# 04_FPGA_core.net
KiCad netlist of a schematic drawn in Altium Designer
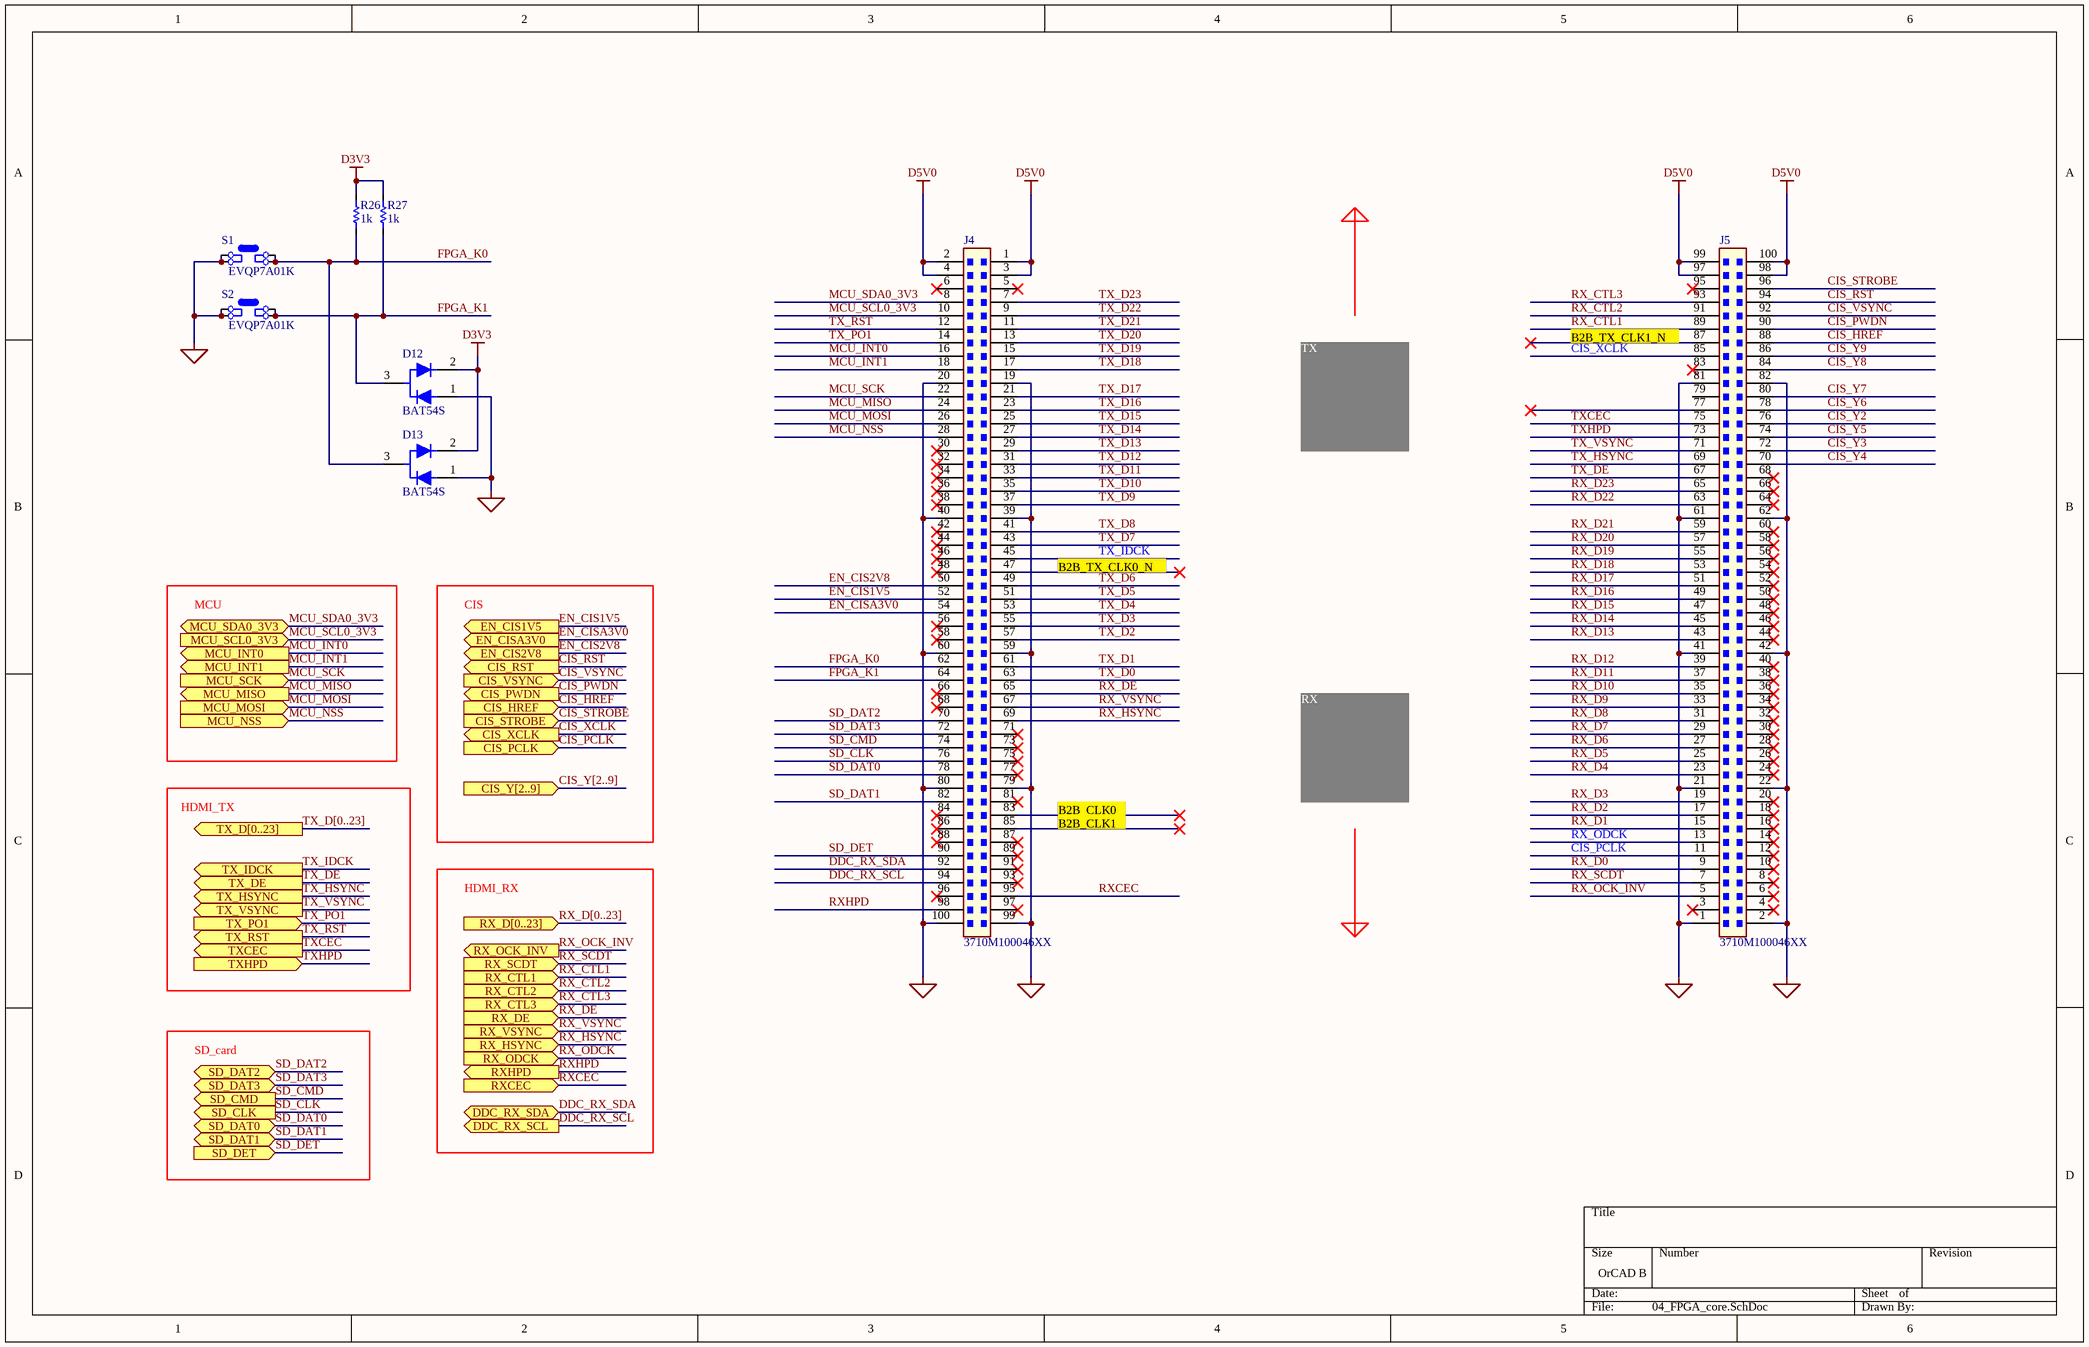
[diagram p0: 04_FPGA_core.SchDoc]

(export (version "E")
  (design (tool "Eeschema 10.0.6"))
  (components
    (comp (ref "D12")
      (value "BAT54S")
      (footprint "SOT95P230X110-3N_SOT23_BAT54")
      (description "Schottky Double Diodes,30V,200mA,SOT23,a1k2k1a2")
      (libsource (lib "AD15_schlib") (part "BAT54S"))
    )
    (comp (ref "D13")
      (value "BAT54S")
      (footprint "SOT95P230X110-3N_SOT23_BAT54")
      (description "Schottky Double Diodes,30V,200mA,SOT23,a1k2k1a2")
      (libsource (lib "AD15_schlib") (part "BAT54S"))
    )
    (comp (ref "J4")
      (value "3710M100046XX")
      (footprint "3710M100046XX")
      (description "B2B male,100Pin,Vertical,0.8mm Pitch,SMD")
      (libsource (lib "AD15_schlib") (part "3710M100046XX"))
    )
    (comp (ref "J5")
      (value "3710M100046XX")
      (footprint "3710M100046XX")
      (description "B2B male,100Pin,Vertical,0.8mm Pitch,SMD")
      (libsource (lib "AD15_schlib") (part "3710M100046XX"))
    )
    (comp (ref "R26")
      (value "1k")
      (footprint "R0402")
      (description "RES,1k,1%,1/16W,0402")
      (libsource (lib "R0402") (part "RES011"))
    )
    (comp (ref "R27")
      (value "1k")
      (footprint "R0402")
      (description "RES,1k,1%,1/16W,0402")
      (libsource (lib "R0402") (part "RES011"))
    )
    (comp (ref "S1")
      (value "EVQP7A01K")
      (footprint "EVQP7A01K")
      (description "Switch,3.5x2.9,Normal open,SMD")
      (libsource (lib "AD15_libpkg") (part "EVQP7A01K"))
    )
    (comp (ref "S2")
      (value "EVQP7A01K")
      (footprint "EVQP7A01K")
      (description "Switch,3.5x2.9,Normal open,SMD")
      (libsource (lib "AD15_libpkg") (part "EVQP7A01K"))
    )
  )
  (nets
    (net (code "1") (name "/CIS_HREF") (class "Default")
      (node (ref "J5") (pin "88") (pinfunction "88_88") (pintype "passive"))
    )
    (net (code "2") (name "/CIS_PCLK") (class "Default")
      (node (ref "J5") (pin "11") (pinfunction "11_11") (pintype "passive"))
    )
    (net (code "3") (name "/CIS_PWDN") (class "Default")
      (node (ref "J5") (pin "90") (pinfunction "90_90") (pintype "passive"))
    )
    (net (code "4") (name "/CIS_RST") (class "Default")
      (node (ref "J5") (pin "94") (pinfunction "94_94") (pintype "passive"))
    )
    (net (code "5") (name "/CIS_STROBE") (class "Default")
      (node (ref "J5") (pin "96") (pinfunction "96_96") (pintype "passive"))
    )
    (net (code "6") (name "/CIS_VSYNC") (class "Default")
      (node (ref "J5") (pin "92") (pinfunction "92_92") (pintype "passive"))
    )
    (net (code "7") (name "/CIS_XCLK") (class "Default")
      (node (ref "J5") (pin "85") (pinfunction "85_85") (pintype "passive"))
    )
    (net (code "8") (name "/CIS_Y2") (class "Default")
      (node (ref "J5") (pin "76") (pinfunction "76_76") (pintype "passive"))
    )
    (net (code "9") (name "/CIS_Y3") (class "Default")
      (node (ref "J5") (pin "72") (pinfunction "72_72") (pintype "passive"))
    )
    (net (code "10") (name "/CIS_Y4") (class "Default")
      (node (ref "J5") (pin "70") (pinfunction "70_70") (pintype "passive"))
    )
    (net (code "11") (name "/CIS_Y5") (class "Default")
      (node (ref "J5") (pin "74") (pinfunction "74_74") (pintype "passive"))
    )
    (net (code "12") (name "/CIS_Y6") (class "Default")
      (node (ref "J5") (pin "78") (pinfunction "78_78") (pintype "passive"))
    )
    (net (code "13") (name "/CIS_Y7") (class "Default")
      (node (ref "J5") (pin "80") (pinfunction "80_80") (pintype "passive"))
    )
    (net (code "14") (name "/CIS_Y8") (class "Default")
      (node (ref "J5") (pin "84") (pinfunction "84_84") (pintype "passive"))
    )
    (net (code "15") (name "/CIS_Y9") (class "Default")
      (node (ref "J5") (pin "86") (pinfunction "86_86") (pintype "passive"))
    )
    (net (code "17") (name "/DDC_RX_SCL") (class "Default")
      (node (ref "J4") (pin "94") (pinfunction "94_94") (pintype "passive"))
    )
    (net (code "18") (name "/DDC_RX_SDA") (class "Default")
      (node (ref "J4") (pin "92") (pinfunction "92_92") (pintype "passive"))
    )
    (net (code "19") (name "/EN_CIS1V5") (class "Default")
      (node (ref "J4") (pin "52") (pinfunction "52_52") (pintype "passive"))
    )
    (net (code "20") (name "/EN_CIS2V8") (class "Default")
      (node (ref "J4") (pin "50") (pinfunction "50_50") (pintype "passive"))
    )
    (net (code "21") (name "/EN_CISA3V0") (class "Default")
      (node (ref "J4") (pin "54") (pinfunction "54_54") (pintype "passive"))
    )
    (net (code "22") (name "/FPGA_K0") (class "Default")
      (node (ref "D13") (pin "3") (pinfunction "2_3") (pintype "passive"))
      (node (ref "J4") (pin "62") (pinfunction "62_62") (pintype "passive"))
      (node (ref "R26") (pin "1") (pinfunction "0_1") (pintype "passive"))
      (node (ref "S1") (pin "2") (pinfunction "CVdd_2") (pintype "passive"))
    )
    (net (code "23") (name "/FPGA_K1") (class "Default")
      (node (ref "D12") (pin "3") (pinfunction "2_3") (pintype "passive"))
      (node (ref "J4") (pin "64") (pinfunction "64_64") (pintype "passive"))
      (node (ref "R27") (pin "1") (pinfunction "0_1") (pintype "passive"))
      (node (ref "S2") (pin "2") (pinfunction "CVdd_2") (pintype "passive"))
    )
    (net (code "24") (name "/MCU_INT0") (class "Default")
      (node (ref "J4") (pin "16") (pinfunction "16_16") (pintype "passive"))
    )
    (net (code "25") (name "/MCU_INT1") (class "Default")
      (node (ref "J4") (pin "18") (pinfunction "18_18") (pintype "passive"))
    )
    (net (code "26") (name "/MCU_MISO") (class "Default")
      (node (ref "J4") (pin "24") (pinfunction "24_24") (pintype "passive"))
    )
    (net (code "27") (name "/MCU_MOSI") (class "Default")
      (node (ref "J4") (pin "26") (pinfunction "26_26") (pintype "passive"))
    )
    (net (code "28") (name "/MCU_NSS") (class "Default")
      (node (ref "J4") (pin "28") (pinfunction "28_28") (pintype "passive"))
    )
    (net (code "29") (name "/MCU_SCK") (class "Default")
      (node (ref "J4") (pin "22") (pinfunction "22_22") (pintype "passive"))
    )
    (net (code "30") (name "/MCU_SCL0_3V3") (class "Default")
      (node (ref "J4") (pin "10") (pinfunction "9_10") (pintype "passive"))
    )
    (net (code "31") (name "/MCU_SDA0_3V3") (class "Default")
      (node (ref "J4") (pin "8") (pinfunction "7_8") (pintype "passive"))
    )
    (net (code "32") (name "/RXCEC") (class "Default")
      (node (ref "J4") (pin "95") (pinfunction "95_95") (pintype "passive"))
    )
    (net (code "33") (name "/RXHPD") (class "Default")
      (node (ref "J4") (pin "98") (pinfunction "98_98") (pintype "passive"))
    )
    (net (code "34") (name "/RX_CTL1") (class "Default")
      (node (ref "J5") (pin "89") (pinfunction "89_89") (pintype "passive"))
    )
    (net (code "35") (name "/RX_CTL2") (class "Default")
      (node (ref "J5") (pin "91") (pinfunction "91_91") (pintype "passive"))
    )
    (net (code "36") (name "/RX_CTL3") (class "Default")
      (node (ref "J5") (pin "93") (pinfunction "93_93") (pintype "passive"))
    )
    (net (code "37") (name "/RX_D0") (class "Default")
      (node (ref "J5") (pin "9") (pinfunction "8_9") (pintype "passive"))
    )
    (net (code "38") (name "/RX_D1") (class "Default")
      (node (ref "J5") (pin "15") (pinfunction "15_15") (pintype "passive"))
    )
    (net (code "39") (name "/RX_D2") (class "Default")
      (node (ref "J5") (pin "17") (pinfunction "17_17") (pintype "passive"))
    )
    (net (code "40") (name "/RX_D3") (class "Default")
      (node (ref "J5") (pin "19") (pinfunction "19_19") (pintype "passive"))
    )
    (net (code "41") (name "/RX_D4") (class "Default")
      (node (ref "J5") (pin "23") (pinfunction "23_23") (pintype "passive"))
    )
    (net (code "42") (name "/RX_D5") (class "Default")
      (node (ref "J5") (pin "25") (pinfunction "25_25") (pintype "passive"))
    )
    (net (code "43") (name "/RX_D6") (class "Default")
      (node (ref "J5") (pin "27") (pinfunction "27_27") (pintype "passive"))
    )
    (net (code "44") (name "/RX_D7") (class "Default")
      (node (ref "J5") (pin "29") (pinfunction "29_29") (pintype "passive"))
    )
    (net (code "45") (name "/RX_D8") (class "Default")
      (node (ref "J5") (pin "31") (pinfunction "31_31") (pintype "passive"))
    )
    (net (code "46") (name "/RX_D9") (class "Default")
      (node (ref "J5") (pin "33") (pinfunction "33_33") (pintype "passive"))
    )
    (net (code "47") (name "/RX_D10") (class "Default")
      (node (ref "J5") (pin "35") (pinfunction "35_35") (pintype "passive"))
    )
    (net (code "48") (name "/RX_D11") (class "Default")
      (node (ref "J5") (pin "37") (pinfunction "37_37") (pintype "passive"))
    )
    (net (code "49") (name "/RX_D12") (class "Default")
      (node (ref "J5") (pin "39") (pinfunction "39_39") (pintype "passive"))
    )
    (net (code "50") (name "/RX_D13") (class "Default")
      (node (ref "J5") (pin "43") (pinfunction "43_43") (pintype "passive"))
    )
    (net (code "51") (name "/RX_D14") (class "Default")
      (node (ref "J5") (pin "45") (pinfunction "45_45") (pintype "passive"))
    )
    (net (code "52") (name "/RX_D15") (class "Default")
      (node (ref "J5") (pin "47") (pinfunction "47_47") (pintype "passive"))
    )
    (net (code "53") (name "/RX_D16") (class "Default")
      (node (ref "J5") (pin "49") (pinfunction "49_49") (pintype "passive"))
    )
    (net (code "54") (name "/RX_D17") (class "Default")
      (node (ref "J5") (pin "51") (pinfunction "51_51") (pintype "passive"))
    )
    (net (code "55") (name "/RX_D18") (class "Default")
      (node (ref "J5") (pin "53") (pinfunction "53_53") (pintype "passive"))
    )
    (net (code "56") (name "/RX_D19") (class "Default")
      (node (ref "J5") (pin "55") (pinfunction "55_55") (pintype "passive"))
    )
    (net (code "57") (name "/RX_D20") (class "Default")
      (node (ref "J5") (pin "57") (pinfunction "57_57") (pintype "passive"))
    )
    (net (code "58") (name "/RX_D21") (class "Default")
      (node (ref "J5") (pin "59") (pinfunction "59_59") (pintype "passive"))
    )
    (net (code "59") (name "/RX_D22") (class "Default")
      (node (ref "J5") (pin "63") (pinfunction "63_63") (pintype "passive"))
    )
    (net (code "60") (name "/RX_D23") (class "Default")
      (node (ref "J5") (pin "65") (pinfunction "65_65") (pintype "passive"))
    )
    (net (code "61") (name "/RX_DE") (class "Default")
      (node (ref "J4") (pin "65") (pinfunction "65_65") (pintype "passive"))
    )
    (net (code "63") (name "/RX_HSYNC") (class "Default")
      (node (ref "J4") (pin "69") (pinfunction "69_69") (pintype "passive"))
    )
    (net (code "64") (name "/RX_OCK_INV") (class "Default")
      (node (ref "J5") (pin "5") (pinfunction "4_5") (pintype "passive"))
    )
    (net (code "65") (name "/RX_ODCK") (class "Default")
      (node (ref "J5") (pin "13") (pinfunction "13_13") (pintype "passive"))
    )
    (net (code "66") (name "/RX_SCDT") (class "Default")
      (node (ref "J5") (pin "7") (pinfunction "6_7") (pintype "passive"))
    )
    (net (code "67") (name "/RX_VSYNC") (class "Default")
      (node (ref "J4") (pin "67") (pinfunction "67_67") (pintype "passive"))
    )
    (net (code "68") (name "/SD_CLK") (class "Default")
      (node (ref "J4") (pin "76") (pinfunction "76_76") (pintype "passive"))
    )
    (net (code "69") (name "/SD_CMD") (class "Default")
      (node (ref "J4") (pin "74") (pinfunction "74_74") (pintype "passive"))
    )
    (net (code "70") (name "/SD_DAT0") (class "Default")
      (node (ref "J4") (pin "78") (pinfunction "78_78") (pintype "passive"))
    )
    (net (code "71") (name "/SD_DAT1") (class "Default")
      (node (ref "J4") (pin "82") (pinfunction "82_82") (pintype "passive"))
    )
    (net (code "72") (name "/SD_DAT2") (class "Default")
      (node (ref "J4") (pin "70") (pinfunction "70_70") (pintype "passive"))
    )
    (net (code "73") (name "/SD_DAT3") (class "Default")
      (node (ref "J4") (pin "72") (pinfunction "72_72") (pintype "passive"))
    )
    (net (code "74") (name "/SD_DET") (class "Default")
      (node (ref "J4") (pin "90") (pinfunction "90_90") (pintype "passive"))
    )
    (net (code "75") (name "/TXCEC") (class "Default")
      (node (ref "J5") (pin "75") (pinfunction "75_75") (pintype "passive"))
    )
    (net (code "76") (name "/TXHPD") (class "Default")
      (node (ref "J5") (pin "73") (pinfunction "73_73") (pintype "passive"))
    )
    (net (code "77") (name "/TX_D0") (class "Default")
      (node (ref "J4") (pin "63") (pinfunction "63_63") (pintype "passive"))
    )
    (net (code "78") (name "/TX_D1") (class "Default")
      (node (ref "J4") (pin "61") (pinfunction "61_61") (pintype "passive"))
    )
    (net (code "79") (name "/TX_D2") (class "Default")
      (node (ref "J4") (pin "57") (pinfunction "57_57") (pintype "passive"))
    )
    (net (code "80") (name "/TX_D3") (class "Default")
      (node (ref "J4") (pin "55") (pinfunction "55_55") (pintype "passive"))
    )
    (net (code "81") (name "/TX_D4") (class "Default")
      (node (ref "J4") (pin "53") (pinfunction "53_53") (pintype "passive"))
    )
    (net (code "82") (name "/TX_D5") (class "Default")
      (node (ref "J4") (pin "51") (pinfunction "51_51") (pintype "passive"))
    )
    (net (code "83") (name "/TX_D6") (class "Default")
      (node (ref "J4") (pin "49") (pinfunction "49_49") (pintype "passive"))
    )
    (net (code "84") (name "/TX_D7") (class "Default")
      (node (ref "J4") (pin "43") (pinfunction "43_43") (pintype "passive"))
    )
    (net (code "85") (name "/TX_D8") (class "Default")
      (node (ref "J4") (pin "41") (pinfunction "41_41") (pintype "passive"))
    )
    (net (code "86") (name "/TX_D9") (class "Default")
      (node (ref "J4") (pin "37") (pinfunction "37_37") (pintype "passive"))
    )
    (net (code "87") (name "/TX_D10") (class "Default")
      (node (ref "J4") (pin "35") (pinfunction "35_35") (pintype "passive"))
    )
    (net (code "88") (name "/TX_D11") (class "Default")
      (node (ref "J4") (pin "33") (pinfunction "33_33") (pintype "passive"))
    )
    (net (code "89") (name "/TX_D12") (class "Default")
      (node (ref "J4") (pin "31") (pinfunction "31_31") (pintype "passive"))
    )
    (net (code "90") (name "/TX_D13") (class "Default")
      (node (ref "J4") (pin "29") (pinfunction "29_29") (pintype "passive"))
    )
    (net (code "91") (name "/TX_D14") (class "Default")
      (node (ref "J4") (pin "27") (pinfunction "27_27") (pintype "passive"))
    )
    (net (code "92") (name "/TX_D15") (class "Default")
      (node (ref "J4") (pin "25") (pinfunction "25_25") (pintype "passive"))
    )
    (net (code "93") (name "/TX_D16") (class "Default")
      (node (ref "J4") (pin "23") (pinfunction "23_23") (pintype "passive"))
    )
    (net (code "94") (name "/TX_D17") (class "Default")
      (node (ref "J4") (pin "21") (pinfunction "21_21") (pintype "passive"))
    )
    (net (code "95") (name "/TX_D18") (class "Default")
      (node (ref "J4") (pin "17") (pinfunction "17_17") (pintype "passive"))
    )
    (net (code "96") (name "/TX_D19") (class "Default")
      (node (ref "J4") (pin "15") (pinfunction "15_15") (pintype "passive"))
    )
    (net (code "97") (name "/TX_D20") (class "Default")
      (node (ref "J4") (pin "13") (pinfunction "13_13") (pintype "passive"))
    )
    (net (code "98") (name "/TX_D21") (class "Default")
      (node (ref "J4") (pin "11") (pinfunction "11_11") (pintype "passive"))
    )
    (net (code "99") (name "/TX_D22") (class "Default")
      (node (ref "J4") (pin "9") (pinfunction "8_9") (pintype "passive"))
    )
    (net (code "100") (name "/TX_D23") (class "Default")
      (node (ref "J4") (pin "7") (pinfunction "6_7") (pintype "passive"))
    )
    (net (code "101") (name "/TX_DE") (class "Default")
      (node (ref "J5") (pin "67") (pinfunction "67_67") (pintype "passive"))
    )
    (net (code "103") (name "/TX_HSYNC") (class "Default")
      (node (ref "J5") (pin "69") (pinfunction "69_69") (pintype "passive"))
    )
    (net (code "104") (name "/TX_IDCK") (class "Default")
      (node (ref "J4") (pin "45") (pinfunction "45_45") (pintype "passive"))
    )
    (net (code "105") (name "/TX_PO1") (class "Default")
      (node (ref "J4") (pin "14") (pinfunction "14_14") (pintype "passive"))
    )
    (net (code "106") (name "/TX_RST") (class "Default")
      (node (ref "J4") (pin "12") (pinfunction "12_12") (pintype "passive"))
    )
    (net (code "107") (name "/TX_VSYNC") (class "Default")
      (node (ref "J5") (pin "71") (pinfunction "71_71") (pintype "passive"))
    )
    (net (code "108") (name "D3V3") (class "Default")
      (node (ref "D12") (pin "2") (pinfunction "1_2") (pintype "passive"))
      (node (ref "D13") (pin "2") (pinfunction "1_2") (pintype "passive"))
      (node (ref "R26") (pin "2") (pinfunction "2_2") (pintype "passive"))
      (node (ref "R27") (pin "2") (pinfunction "2_2") (pintype "passive"))
    )
    (net (code "109") (name "D5V0") (class "Default")
      (node (ref "J4") (pin "1") (pinfunction "0_1") (pintype "passive"))
      (node (ref "J4") (pin "2") (pinfunction "1_2") (pintype "passive"))
      (node (ref "J4") (pin "3") (pinfunction "2_3") (pintype "passive"))
      (node (ref "J4") (pin "4") (pinfunction "3_4") (pintype "passive"))
      (node (ref "J5") (pin "100") (pinfunction "100_100") (pintype "passive"))
      (node (ref "J5") (pin "97") (pinfunction "97_97") (pintype "passive"))
      (node (ref "J5") (pin "98") (pinfunction "98_98") (pintype "passive"))
      (node (ref "J5") (pin "99") (pinfunction "99_99") (pintype "passive"))
    )
    (net (code "110") (name "GND") (class "Default")
      (node (ref "D12") (pin "1") (pinfunction "0_1") (pintype "passive"))
      (node (ref "D13") (pin "1") (pinfunction "0_1") (pintype "passive"))
      (node (ref "J4") (pin "100") (pinfunction "100_100") (pintype "passive"))
      (node (ref "J4") (pin "19") (pinfunction "19_19") (pintype "passive"))
      (node (ref "J4") (pin "20") (pinfunction "20_20") (pintype "passive"))
      (node (ref "J4") (pin "39") (pinfunction "39_39") (pintype "passive"))
      (node (ref "J4") (pin "40") (pinfunction "40_40") (pintype "passive"))
      (node (ref "J4") (pin "59") (pinfunction "59_59") (pintype "passive"))
      (node (ref "J4") (pin "60") (pinfunction "60_60") (pintype "passive"))
      (node (ref "J4") (pin "79") (pinfunction "79_79") (pintype "passive"))
      (node (ref "J4") (pin "80") (pinfunction "80_80") (pintype "passive"))
      (node (ref "J4") (pin "99") (pinfunction "99_99") (pintype "passive"))
      (node (ref "J5") (pin "1") (pinfunction "0_1") (pintype "passive"))
      (node (ref "J5") (pin "2") (pinfunction "1_2") (pintype "passive"))
      (node (ref "J5") (pin "21") (pinfunction "21_21") (pintype "passive"))
      (node (ref "J5") (pin "22") (pinfunction "22_22") (pintype "passive"))
      (node (ref "J5") (pin "41") (pinfunction "41_41") (pintype "passive"))
      (node (ref "J5") (pin "42") (pinfunction "42_42") (pintype "passive"))
      (node (ref "J5") (pin "61") (pinfunction "61_61") (pintype "passive"))
      (node (ref "J5") (pin "62") (pinfunction "62_62") (pintype "passive"))
      (node (ref "J5") (pin "81") (pinfunction "81_81") (pintype "passive"))
      (node (ref "J5") (pin "82") (pinfunction "82_82") (pintype "passive"))
      (node (ref "S1") (pin "1") (pinfunction "CVdd_1") (pintype "passive"))
      (node (ref "S2") (pin "1") (pinfunction "CVdd_1") (pintype "passive"))
    )
    (net (code "111") (name "unconnected-(J4-4-Pad5)") (class "Default")
      (node (ref "J4") (pin "5") (pinfunction "4_5") (pintype "passive+no_connect"))
    )
    (net (code "112") (name "unconnected-(J4-5-Pad6)") (class "Default")
      (node (ref "J4") (pin "6") (pinfunction "5_6") (pintype "passive+no_connect"))
    )
    (net (code "113") (name "unconnected-(J4-Pad30)") (class "Default")
      (node (ref "J4") (pin "30") (pinfunction "30_30") (pintype "passive+no_connect"))
    )
    (net (code "114") (name "unconnected-(J4-Pad32)") (class "Default")
      (node (ref "J4") (pin "32") (pinfunction "32_32") (pintype "passive+no_connect"))
    )
    (net (code "115") (name "unconnected-(J4-Pad34)") (class "Default")
      (node (ref "J4") (pin "34") (pinfunction "34_34") (pintype "passive+no_connect"))
    )
    (net (code "116") (name "unconnected-(J4-Pad36)") (class "Default")
      (node (ref "J4") (pin "36") (pinfunction "36_36") (pintype "passive+no_connect"))
    )
    (net (code "117") (name "unconnected-(J4-Pad38)") (class "Default")
      (node (ref "J4") (pin "38") (pinfunction "38_38") (pintype "passive+no_connect"))
    )
    (net (code "118") (name "unconnected-(J4-Pad42)") (class "Default")
      (node (ref "J4") (pin "42") (pinfunction "42_42") (pintype "passive+no_connect"))
    )
    (net (code "119") (name "unconnected-(J4-Pad44)") (class "Default")
      (node (ref "J4") (pin "44") (pinfunction "44_44") (pintype "passive+no_connect"))
    )
    (net (code "120") (name "unconnected-(J4-Pad46)") (class "Default")
      (node (ref "J4") (pin "46") (pinfunction "46_46") (pintype "passive+no_connect"))
    )
    (net (code "121") (name "unconnected-(J4-Pad47)") (class "Default")
      (node (ref "J4") (pin "47") (pinfunction "47_47") (pintype "passive+no_connect"))
    )
    (net (code "122") (name "unconnected-(J4-Pad48)") (class "Default")
      (node (ref "J4") (pin "48") (pinfunction "48_48") (pintype "passive+no_connect"))
    )
    (net (code "123") (name "unconnected-(J4-Pad56)") (class "Default")
      (node (ref "J4") (pin "56") (pinfunction "56_56") (pintype "passive+no_connect"))
    )
    (net (code "124") (name "unconnected-(J4-Pad58)") (class "Default")
      (node (ref "J4") (pin "58") (pinfunction "58_58") (pintype "passive+no_connect"))
    )
    (net (code "125") (name "unconnected-(J4-Pad66)") (class "Default")
      (node (ref "J4") (pin "66") (pinfunction "66_66") (pintype "passive+no_connect"))
    )
    (net (code "126") (name "unconnected-(J4-Pad68)") (class "Default")
      (node (ref "J4") (pin "68") (pinfunction "68_68") (pintype "passive+no_connect"))
    )
    (net (code "127") (name "unconnected-(J4-Pad71)") (class "Default")
      (node (ref "J4") (pin "71") (pinfunction "71_71") (pintype "passive+no_connect"))
    )
    (net (code "128") (name "unconnected-(J4-Pad73)") (class "Default")
      (node (ref "J4") (pin "73") (pinfunction "73_73") (pintype "passive+no_connect"))
    )
    (net (code "129") (name "unconnected-(J4-Pad75)") (class "Default")
      (node (ref "J4") (pin "75") (pinfunction "75_75") (pintype "passive+no_connect"))
    )
    (net (code "130") (name "unconnected-(J4-Pad77)") (class "Default")
      (node (ref "J4") (pin "77") (pinfunction "77_77") (pintype "passive+no_connect"))
    )
    (net (code "131") (name "unconnected-(J4-Pad81)") (class "Default")
      (node (ref "J4") (pin "81") (pinfunction "81_81") (pintype "passive+no_connect"))
    )
    (net (code "132") (name "unconnected-(J4-Pad83)") (class "Default")
      (node (ref "J4") (pin "83") (pinfunction "83_83") (pintype "passive+no_connect"))
    )
    (net (code "133") (name "unconnected-(J4-Pad84)") (class "Default")
      (node (ref "J4") (pin "84") (pinfunction "84_84") (pintype "passive+no_connect"))
    )
    (net (code "134") (name "unconnected-(J4-Pad85)") (class "Default")
      (node (ref "J4") (pin "85") (pinfunction "85_85") (pintype "passive+no_connect"))
    )
    (net (code "135") (name "unconnected-(J4-Pad86)") (class "Default")
      (node (ref "J4") (pin "86") (pinfunction "86_86") (pintype "passive+no_connect"))
    )
    (net (code "136") (name "unconnected-(J4-Pad87)") (class "Default")
      (node (ref "J4") (pin "87") (pinfunction "87_87") (pintype "passive+no_connect"))
    )
    (net (code "137") (name "unconnected-(J4-Pad88)") (class "Default")
      (node (ref "J4") (pin "88") (pinfunction "88_88") (pintype "passive+no_connect"))
    )
    (net (code "138") (name "unconnected-(J4-Pad89)") (class "Default")
      (node (ref "J4") (pin "89") (pinfunction "89_89") (pintype "passive+no_connect"))
    )
    (net (code "139") (name "unconnected-(J4-Pad91)") (class "Default")
      (node (ref "J4") (pin "91") (pinfunction "91_91") (pintype "passive+no_connect"))
    )
    (net (code "140") (name "unconnected-(J4-Pad93)") (class "Default")
      (node (ref "J4") (pin "93") (pinfunction "93_93") (pintype "passive+no_connect"))
    )
    (net (code "141") (name "unconnected-(J4-Pad96)") (class "Default")
      (node (ref "J4") (pin "96") (pinfunction "96_96") (pintype "passive+no_connect"))
    )
    (net (code "142") (name "unconnected-(J4-Pad97)") (class "Default")
      (node (ref "J4") (pin "97") (pinfunction "97_97") (pintype "passive+no_connect"))
    )
    (net (code "143") (name "unconnected-(J5-2-Pad3)") (class "Default")
      (node (ref "J5") (pin "3") (pinfunction "2_3") (pintype "passive+no_connect"))
    )
    (net (code "144") (name "unconnected-(J5-3-Pad4)") (class "Default")
      (node (ref "J5") (pin "4") (pinfunction "3_4") (pintype "passive+no_connect"))
    )
    (net (code "145") (name "unconnected-(J5-5-Pad6)") (class "Default")
      (node (ref "J5") (pin "6") (pinfunction "5_6") (pintype "passive+no_connect"))
    )
    (net (code "146") (name "unconnected-(J5-7-Pad8)") (class "Default")
      (node (ref "J5") (pin "8") (pinfunction "7_8") (pintype "passive+no_connect"))
    )
    (net (code "147") (name "unconnected-(J5-9-Pad10)") (class "Default")
      (node (ref "J5") (pin "10") (pinfunction "9_10") (pintype "passive+no_connect"))
    )
    (net (code "148") (name "unconnected-(J5-Pad12)") (class "Default")
      (node (ref "J5") (pin "12") (pinfunction "12_12") (pintype "passive+no_connect"))
    )
    (net (code "149") (name "unconnected-(J5-Pad14)") (class "Default")
      (node (ref "J5") (pin "14") (pinfunction "14_14") (pintype "passive+no_connect"))
    )
    (net (code "150") (name "unconnected-(J5-Pad16)") (class "Default")
      (node (ref "J5") (pin "16") (pinfunction "16_16") (pintype "passive+no_connect"))
    )
    (net (code "151") (name "unconnected-(J5-Pad18)") (class "Default")
      (node (ref "J5") (pin "18") (pinfunction "18_18") (pintype "passive+no_connect"))
    )
    (net (code "152") (name "unconnected-(J5-Pad20)") (class "Default")
      (node (ref "J5") (pin "20") (pinfunction "20_20") (pintype "passive+no_connect"))
    )
    (net (code "153") (name "unconnected-(J5-Pad24)") (class "Default")
      (node (ref "J5") (pin "24") (pinfunction "24_24") (pintype "passive+no_connect"))
    )
    (net (code "154") (name "unconnected-(J5-Pad26)") (class "Default")
      (node (ref "J5") (pin "26") (pinfunction "26_26") (pintype "passive+no_connect"))
    )
    (net (code "155") (name "unconnected-(J5-Pad28)") (class "Default")
      (node (ref "J5") (pin "28") (pinfunction "28_28") (pintype "passive+no_connect"))
    )
    (net (code "156") (name "unconnected-(J5-Pad30)") (class "Default")
      (node (ref "J5") (pin "30") (pinfunction "30_30") (pintype "passive+no_connect"))
    )
    (net (code "157") (name "unconnected-(J5-Pad32)") (class "Default")
      (node (ref "J5") (pin "32") (pinfunction "32_32") (pintype "passive+no_connect"))
    )
    (net (code "158") (name "unconnected-(J5-Pad34)") (class "Default")
      (node (ref "J5") (pin "34") (pinfunction "34_34") (pintype "passive+no_connect"))
    )
    (net (code "159") (name "unconnected-(J5-Pad36)") (class "Default")
      (node (ref "J5") (pin "36") (pinfunction "36_36") (pintype "passive+no_connect"))
    )
    (net (code "160") (name "unconnected-(J5-Pad38)") (class "Default")
      (node (ref "J5") (pin "38") (pinfunction "38_38") (pintype "passive+no_connect"))
    )
    (net (code "161") (name "unconnected-(J5-Pad40)") (class "Default")
      (node (ref "J5") (pin "40") (pinfunction "40_40") (pintype "passive+no_connect"))
    )
    (net (code "162") (name "unconnected-(J5-Pad44)") (class "Default")
      (node (ref "J5") (pin "44") (pinfunction "44_44") (pintype "passive+no_connect"))
    )
    (net (code "163") (name "unconnected-(J5-Pad46)") (class "Default")
      (node (ref "J5") (pin "46") (pinfunction "46_46") (pintype "passive+no_connect"))
    )
    (net (code "164") (name "unconnected-(J5-Pad48)") (class "Default")
      (node (ref "J5") (pin "48") (pinfunction "48_48") (pintype "passive+no_connect"))
    )
    (net (code "165") (name "unconnected-(J5-Pad50)") (class "Default")
      (node (ref "J5") (pin "50") (pinfunction "50_50") (pintype "passive+no_connect"))
    )
    (net (code "166") (name "unconnected-(J5-Pad52)") (class "Default")
      (node (ref "J5") (pin "52") (pinfunction "52_52") (pintype "passive+no_connect"))
    )
    (net (code "167") (name "unconnected-(J5-Pad54)") (class "Default")
      (node (ref "J5") (pin "54") (pinfunction "54_54") (pintype "passive+no_connect"))
    )
    (net (code "168") (name "unconnected-(J5-Pad56)") (class "Default")
      (node (ref "J5") (pin "56") (pinfunction "56_56") (pintype "passive+no_connect"))
    )
    (net (code "169") (name "unconnected-(J5-Pad58)") (class "Default")
      (node (ref "J5") (pin "58") (pinfunction "58_58") (pintype "passive+no_connect"))
    )
    (net (code "170") (name "unconnected-(J5-Pad60)") (class "Default")
      (node (ref "J5") (pin "60") (pinfunction "60_60") (pintype "passive+no_connect"))
    )
    (net (code "171") (name "unconnected-(J5-Pad64)") (class "Default")
      (node (ref "J5") (pin "64") (pinfunction "64_64") (pintype "passive+no_connect"))
    )
    (net (code "172") (name "unconnected-(J5-Pad66)") (class "Default")
      (node (ref "J5") (pin "66") (pinfunction "66_66") (pintype "passive+no_connect"))
    )
    (net (code "173") (name "unconnected-(J5-Pad68)") (class "Default")
      (node (ref "J5") (pin "68") (pinfunction "68_68") (pintype "passive+no_connect"))
    )
    (net (code "174") (name "unconnected-(J5-Pad77)") (class "Default")
      (node (ref "J5") (pin "77") (pinfunction "77_77") (pintype "passive+no_connect"))
    )
    (net (code "175") (name "unconnected-(J5-Pad79)") (class "Default")
      (node (ref "J5") (pin "79") (pinfunction "79_79") (pintype "passive"))
    )
    (net (code "176") (name "unconnected-(J5-Pad83)") (class "Default")
      (node (ref "J5") (pin "83") (pinfunction "83_83") (pintype "passive+no_connect"))
    )
    (net (code "177") (name "unconnected-(J5-Pad87)") (class "Default")
      (node (ref "J5") (pin "87") (pinfunction "87_87") (pintype "passive+no_connect"))
    )
    (net (code "178") (name "unconnected-(J5-Pad95)") (class "Default")
      (node (ref "J5") (pin "95") (pinfunction "95_95") (pintype "passive+no_connect"))
    )
  )
)
